# Front_Node_KKmolex.net
KiCad netlist of a schematic drawn in EAGLE
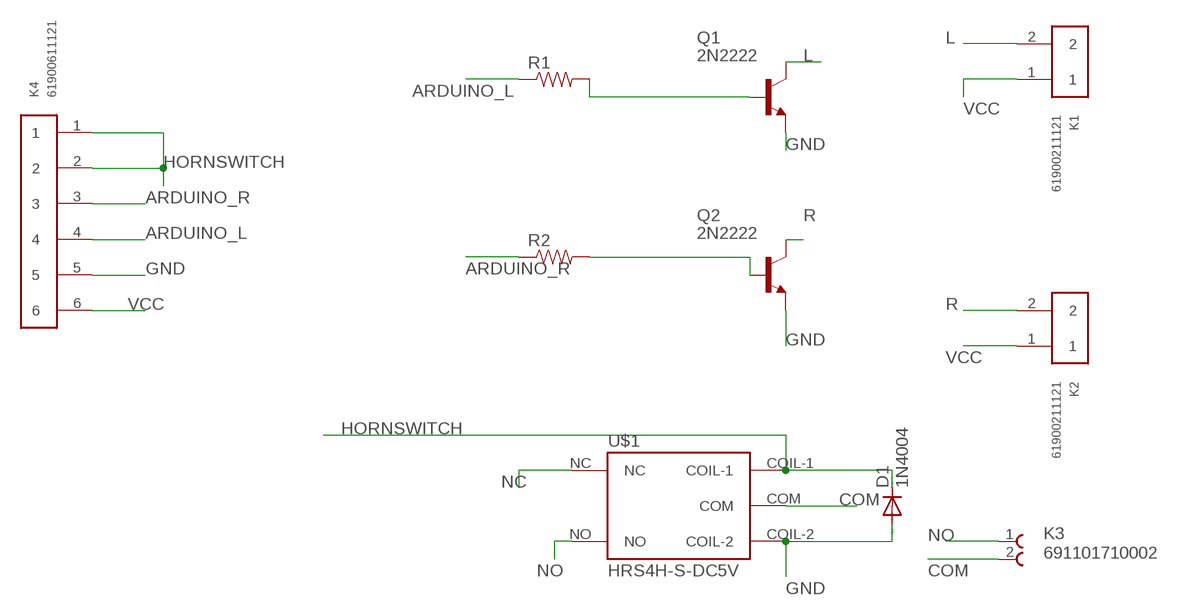
[diagram p0: schematic, sheet 1]

(export (version "E")
  (design (tool "Eeschema 10.0.6"))
  (components
    (comp (ref "D1")
      (value "1N4004")
      (footprint "eagle-import:DO41-10")
      (libsource (lib "eagle-import") (part "1N4004"))
    )
    (comp (ref "K1")
      (value "61900211121")
      (footprint "eagle-import:61900211121")
      (libsource (lib "eagle-import") (part "61900211121"))
    )
    (comp (ref "K2")
      (value "61900211121")
      (footprint "eagle-import:61900211121")
      (libsource (lib "eagle-import") (part "61900211121"))
    )
    (comp (ref "K3")
      (value "691101710002")
      (footprint "eagle-import:691101710002")
      (libsource (lib "eagle-import") (part "691101710002"))
    )
    (comp (ref "K4")
      (value "61900611121")
      (footprint "eagle-import:61900611121")
      (libsource (lib "eagle-import") (part "61900611121"))
    )
    (comp (ref "Q1")
      (value "2N2222")
      (footprint "eagle-import:TO18")
      (libsource (lib "eagle-import") (part "2N2222"))
    )
    (comp (ref "Q2")
      (value "2N2222")
      (footprint "eagle-import:TO18")
      (libsource (lib "eagle-import") (part "2N2222"))
    )
    (comp (ref "R1")
      (value "RESISTORPTH-1/4W")
      (footprint "eagle-import:AXIAL-0.4")
      (libsource (lib "eagle-import") (part "RESISTORPTH-1/4W"))
    )
    (comp (ref "R2")
      (value "RESISTORPTH-1/4W")
      (footprint "eagle-import:AXIAL-0.4")
      (libsource (lib "eagle-import") (part "RESISTORPTH-1/4W"))
    )
    (comp (ref "U$1")
      (value "HRS4H-S-DC5V")
      (footprint "eagle-import:RELAY")
      (libsource (lib "eagle-import") (part "HRS4H-S-DC5V"))
    )
  )
  (nets
    (net (code "1") (name "/ARDUINO_L") (class "Default")
      (node (ref "K4") (pin "4") (pinfunction "4_4") (pintype "bidirectional"))
      (node (ref "R1") (pin "P$1") (pinfunction "1_P$1") (pintype "passive"))
    )
    (net (code "2") (name "/ARDUINO_R") (class "Default")
      (node (ref "K4") (pin "3") (pinfunction "3_3") (pintype "bidirectional"))
      (node (ref "R2") (pin "P$1") (pinfunction "1_P$1") (pintype "passive"))
    )
    (net (code "3") (name "/COM") (class "Default")
      (node (ref "K3") (pin "2") (pinfunction "2_2") (pintype "passive"))
      (node (ref "U$1") (pin "COM") (pinfunction "COM_COM") (pintype "bidirectional"))
    )
    (net (code "4") (name "/GND") (class "Default")
      (node (ref "D1") (pin "A") (pinfunction "A_A") (pintype "passive"))
      (node (ref "K4") (pin "5") (pinfunction "5_5") (pintype "bidirectional"))
      (node (ref "Q1") (pin "1") (pinfunction "E_1") (pintype "passive"))
      (node (ref "Q2") (pin "1") (pinfunction "E_1") (pintype "passive"))
      (node (ref "U$1") (pin "COIL-2") (pinfunction "COIL-2_COIL-2") (pintype "power_in"))
    )
    (net (code "5") (name "/HORNSWITCH") (class "Default")
      (node (ref "D1") (pin "C") (pinfunction "C_C") (pintype "passive"))
      (node (ref "K4") (pin "1") (pinfunction "1_1") (pintype "bidirectional"))
      (node (ref "K4") (pin "2") (pinfunction "2_2") (pintype "bidirectional"))
      (node (ref "U$1") (pin "COIL-1") (pinfunction "COIL-1_COIL-1") (pintype "power_in"))
    )
    (net (code "6") (name "/L") (class "Default")
      (node (ref "K1") (pin "2") (pinfunction "2_2") (pintype "bidirectional"))
      (node (ref "Q1") (pin "3") (pinfunction "C_3") (pintype "passive"))
    )
    (net (code "7") (name "/NC") (class "Default")
      (node (ref "U$1") (pin "NC") (pinfunction "NC_NC") (pintype "bidirectional"))
    )
    (net (code "8") (name "/NO") (class "Default")
      (node (ref "K3") (pin "1") (pinfunction "1_1") (pintype "passive"))
      (node (ref "U$1") (pin "NO") (pinfunction "NO_NO") (pintype "bidirectional"))
    )
    (net (code "9") (name "/R") (class "Default")
      (node (ref "K2") (pin "2") (pinfunction "2_2") (pintype "bidirectional"))
      (node (ref "Q2") (pin "3") (pinfunction "C_3") (pintype "passive"))
    )
    (net (code "10") (name "/VCC") (class "Default")
      (node (ref "K1") (pin "1") (pinfunction "1_1") (pintype "bidirectional"))
      (node (ref "K2") (pin "1") (pinfunction "1_1") (pintype "bidirectional"))
      (node (ref "K4") (pin "6") (pinfunction "6_6") (pintype "bidirectional"))
    )
    (net (code "11") (name "Net-(Q1-B)") (class "Default")
      (node (ref "Q1") (pin "2") (pinfunction "B_2") (pintype "passive"))
      (node (ref "R1") (pin "P$2") (pinfunction "2_P$2") (pintype "passive"))
    )
    (net (code "12") (name "Net-(Q2-B)") (class "Default")
      (node (ref "Q2") (pin "2") (pinfunction "B_2") (pintype "passive"))
      (node (ref "R2") (pin "P$2") (pinfunction "2_P$2") (pintype "passive"))
    )
  )
)
